# simple-servo.net
KiCad netlist of a schematic drawn in EAGLE
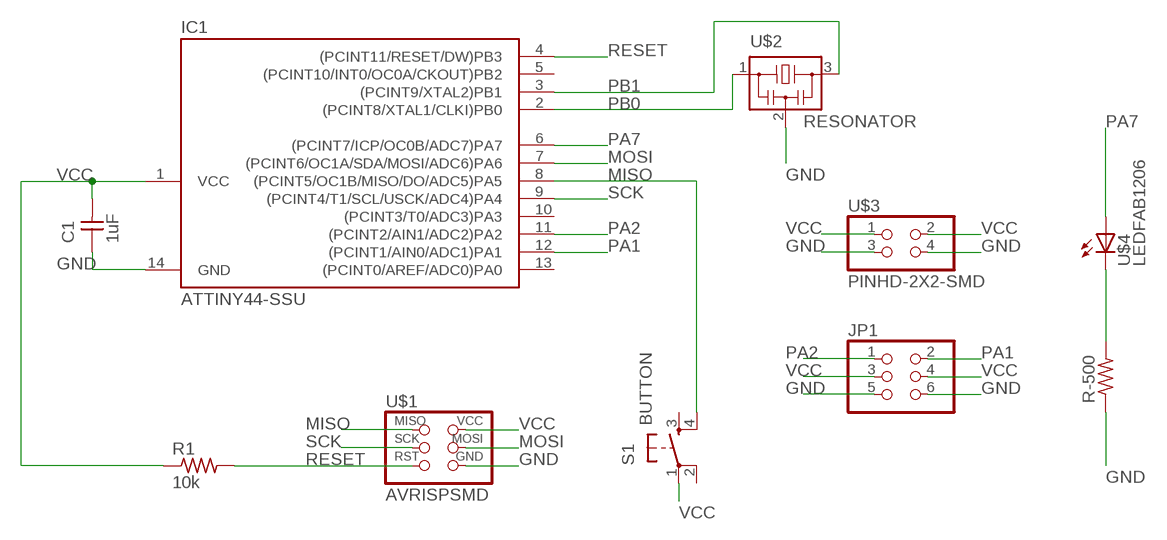
[diagram p0: schematic, sheet 1]

(export (version "E")
  (design (tool "Eeschema 10.0.6"))
  (components
    (comp (ref "C1")
      (value "1uF")
      (footprint "eagle-import:C1206FAB")
      (libsource (lib "eagle-import") (part "CAP-UNPOLARIZEDFAB"))
    )
    (comp (ref "IC1")
      (value "ATTINY44-SSU")
      (footprint "eagle-import:SOIC14")
      (libsource (lib "eagle-import") (part "ATTINY44-SSU"))
    )
    (comp (ref "JP1")
      (value "PINHD-2X3-SMD")
      (footprint "eagle-import:2X03SMD")
      (libsource (lib "eagle-import") (part "PINHD-2X3-SMD"))
    )
    (comp (ref "R-500")
      (value "RES-US1206FAB")
      (footprint "eagle-import:R1206FAB")
      (libsource (lib "eagle-import") (part "RES-US1206FAB"))
    )
    (comp (ref "R1")
      (value "10k")
      (footprint "eagle-import:R1206FAB")
      (libsource (lib "eagle-import") (part "RES-US1206FAB"))
    )
    (comp (ref "S1")
      (value "BUTTON")
      (footprint "eagle-import:6MM_SWITCH")
      (libsource (lib "eagle-import") (part "6MM_SWITCH6MM_SWITCH"))
    )
    (comp (ref "U$1")
      (value "AVRISPSMD")
      (footprint "eagle-import:2X03SMD")
      (libsource (lib "eagle-import") (part "AVRISPSMD"))
    )
    (comp (ref "U$2")
      (value "RESONATOR")
      (footprint "eagle-import:EFOBM")
      (libsource (lib "eagle-import") (part "RESONATOR"))
    )
    (comp (ref "U$3")
      (value "PINHD-2X2-SMD")
      (footprint "eagle-import:2X02SMD")
      (libsource (lib "eagle-import") (part "PINHD-2X2-SMD"))
    )
    (comp (ref "U$4")
      (value "LEDFAB1206")
      (footprint "eagle-import:LED1206FAB")
      (libsource (lib "eagle-import") (part "LEDFAB1206"))
    )
  )
  (nets
    (net (code "1") (name "/GND") (class "Default")
      (node (ref "C1") (pin "1") (pinfunction "1_1") (pintype "passive"))
      (node (ref "IC1") (pin "14") (pinfunction "GND_14") (pintype "power_in"))
      (node (ref "JP1") (pin "5") (pinfunction "5_5") (pintype "passive"))
      (node (ref "JP1") (pin "6") (pinfunction "6_6") (pintype "passive"))
      (node (ref "R-500") (pin "1") (pinfunction "1_1") (pintype "passive"))
      (node (ref "U$1") (pin "6") (pinfunction "GND_6") (pintype "passive"))
      (node (ref "U$2") (pin "2") (pinfunction "2_2") (pintype "passive"))
      (node (ref "U$3") (pin "3") (pinfunction "3_3") (pintype "passive"))
      (node (ref "U$3") (pin "4") (pinfunction "4_4") (pintype "passive"))
    )
    (net (code "2") (name "/MISO") (class "Default")
      (node (ref "IC1") (pin "8") (pinfunction "(PCINT5/OC1B/MISO/DO/ADC5)PA5_8") (pintype "bidirectional"))
      (node (ref "S1") (pin "4") (pinfunction "S1_4") (pintype "passive"))
      (node (ref "U$1") (pin "1") (pinfunction "MISO_1") (pintype "passive"))
    )
    (net (code "3") (name "/MOSI") (class "Default")
      (node (ref "IC1") (pin "7") (pinfunction "(PCINT6/OC1A/SDA/MOSI/ADC6)PA6_7") (pintype "bidirectional"))
      (node (ref "U$1") (pin "4") (pinfunction "MOSI_4") (pintype "passive"))
    )
    (net (code "4") (name "/PA1") (class "Default")
      (node (ref "IC1") (pin "12") (pinfunction "(PCINT1/AIN0/ADC1)PA1_12") (pintype "bidirectional"))
      (node (ref "JP1") (pin "2") (pinfunction "2_2") (pintype "passive"))
    )
    (net (code "5") (name "/PA2") (class "Default")
      (node (ref "IC1") (pin "11") (pinfunction "(PCINT2/AIN1/ADC2)PA2_11") (pintype "bidirectional"))
      (node (ref "JP1") (pin "1") (pinfunction "1_1") (pintype "passive"))
    )
    (net (code "6") (name "/PA7") (class "Default")
      (node (ref "IC1") (pin "6") (pinfunction "(PCINT7/ICP/OC0B/ADC7)PA7_6") (pintype "bidirectional"))
      (node (ref "U$4") (pin "1") (pinfunction "A_1") (pintype "passive"))
    )
    (net (code "7") (name "/PB0") (class "Default")
      (node (ref "IC1") (pin "2") (pinfunction "(PCINT8/XTAL1/CLKI)PB0_2") (pintype "bidirectional"))
      (node (ref "U$2") (pin "1") (pinfunction "1_1") (pintype "passive"))
    )
    (net (code "8") (name "/PB1") (class "Default")
      (node (ref "IC1") (pin "3") (pinfunction "(PCINT9/XTAL2)PB1_3") (pintype "bidirectional"))
      (node (ref "U$2") (pin "3") (pinfunction "3_3") (pintype "passive"))
    )
    (net (code "9") (name "/RESET") (class "Default")
      (node (ref "IC1") (pin "4") (pinfunction "(PCINT11/RESET/DW)PB3_4") (pintype "bidirectional"))
      (node (ref "R1") (pin "2") (pinfunction "2_2") (pintype "passive"))
      (node (ref "U$1") (pin "5") (pinfunction "RST_5") (pintype "passive"))
    )
    (net (code "10") (name "/SCK") (class "Default")
      (node (ref "IC1") (pin "9") (pinfunction "(PCINT4/T1/SCL/USCK/ADC4)PA4_9") (pintype "bidirectional"))
      (node (ref "U$1") (pin "3") (pinfunction "SCK_3") (pintype "passive"))
    )
    (net (code "11") (name "/VCC") (class "Default")
      (node (ref "C1") (pin "2") (pinfunction "2_2") (pintype "passive"))
      (node (ref "IC1") (pin "1") (pinfunction "VCC_1") (pintype "power_in"))
      (node (ref "JP1") (pin "3") (pinfunction "3_3") (pintype "passive"))
      (node (ref "JP1") (pin "4") (pinfunction "4_4") (pintype "passive"))
      (node (ref "R1") (pin "1") (pinfunction "1_1") (pintype "passive"))
      (node (ref "S1") (pin "1") (pinfunction "P_1") (pintype "passive"))
      (node (ref "U$1") (pin "2") (pinfunction "VCC_2") (pintype "passive"))
      (node (ref "U$3") (pin "1") (pinfunction "1_1") (pintype "passive"))
      (node (ref "U$3") (pin "2") (pinfunction "2_2") (pintype "passive"))
    )
    (net (code "12") (name "Net-(U$4-C)") (class "Default")
      (node (ref "R-500") (pin "2") (pinfunction "2_2") (pintype "passive"))
      (node (ref "U$4") (pin "2") (pinfunction "C_2") (pintype "passive"))
    )
    (net (code "13") (name "unconnected-(IC1-(PCINT0{slash}AREF{slash}ADC0)PA0-Pad13)") (class "Default")
      (node (ref "IC1") (pin "13") (pinfunction "(PCINT0/AREF/ADC0)PA0_13") (pintype "bidirectional"))
    )
    (net (code "14") (name "unconnected-(IC1-(PCINT3{slash}T0{slash}ADC3)PA3-Pad10)") (class "Default")
      (node (ref "IC1") (pin "10") (pinfunction "(PCINT3/T0/ADC3)PA3_10") (pintype "bidirectional"))
    )
    (net (code "15") (name "unconnected-(IC1-(PCINT10{slash}INT0{slash}OC0A{slash}CKOUT)PB2-Pad5)") (class "Default")
      (node (ref "IC1") (pin "5") (pinfunction "(PCINT10/INT0/OC0A/CKOUT)PB2_5") (pintype "bidirectional"))
    )
    (net (code "16") (name "unconnected-(S1-P1-Pad2)") (class "Default")
      (node (ref "S1") (pin "2") (pinfunction "P1_2") (pintype "passive"))
    )
    (net (code "17") (name "unconnected-(S1-S-Pad3)") (class "Default")
      (node (ref "S1") (pin "3") (pinfunction "S_3") (pintype "passive"))
    )
  )
)
